# Robot_v2.net
KiCad netlist of a schematic drawn in EAGLE
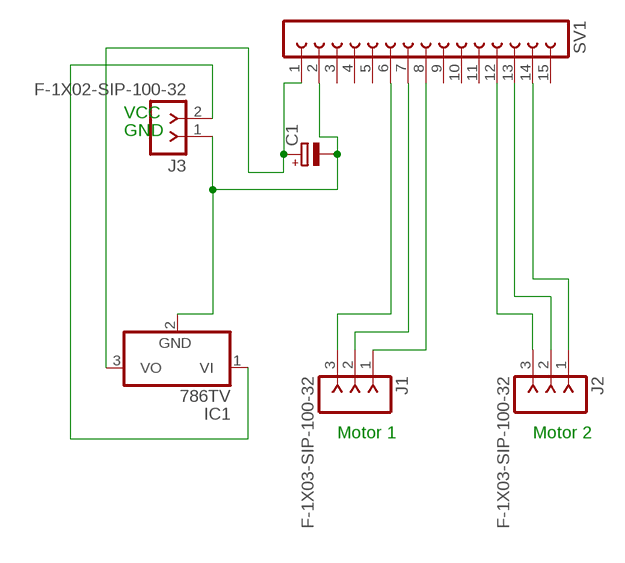
[diagram p0: schematic, sheet 1]

(export (version "E")
  (design (tool "Eeschema 10.0.6"))
  (components
    (comp (ref "C1")
      (value "CPOL-EUE1.8-4")
      (footprint "eagle-import:E1,8-4")
      (libsource (lib "eagle-import") (part "CPOL-EUE1.8-4"))
    )
    (comp (ref "IC1")
      (value "786TV")
      (footprint "eagle-import:TO220V")
      (libsource (lib "eagle-import") (part "78TV6"))
    )
    (comp (ref "J1")
      (value "F-1X03-SIP-100-32")
      (footprint "eagle-import:SIP-100-03-32")
      (libsource (lib "eagle-import") (part "F-1X03-SIP-100-32"))
    )
    (comp (ref "J2")
      (value "F-1X03-SIP-100-32")
      (footprint "eagle-import:SIP-100-03-32")
      (libsource (lib "eagle-import") (part "F-1X03-SIP-100-32"))
    )
    (comp (ref "J3")
      (value "F-1X02-SIP-100-32")
      (footprint "eagle-import:SIP-100-02-32")
      (libsource (lib "eagle-import") (part "F-1X02-SIP-100-32"))
    )
    (comp (ref "SV1")
      (value "FE15-1")
      (footprint "eagle-import:FE15")
      (libsource (lib "eagle-import") (part "FE15-1"))
    )
  )
  (nets
    (net (code "1") (name "Net-(IC1-GND)") (class "Default")
      (node (ref "C1") (pin "-") (pinfunction "-_-") (pintype "passive"))
      (node (ref "IC1") (pin "2") (pinfunction "GND_2") (pintype "passive"))
      (node (ref "J3") (pin "1") (pinfunction "1_1") (pintype "passive"))
      (node (ref "SV1") (pin "2") (pinfunction "2_2") (pintype "passive"))
    )
    (net (code "2") (name "Net-(IC1-VI)") (class "Default")
      (node (ref "IC1") (pin "1") (pinfunction "VI_1") (pintype "input"))
      (node (ref "J3") (pin "2") (pinfunction "2_2") (pintype "passive"))
    )
    (net (code "3") (name "Net-(IC1-VO)") (class "Default")
      (node (ref "C1") (pin "+") (pinfunction "+_+") (pintype "passive"))
      (node (ref "IC1") (pin "3") (pinfunction "VO_3") (pintype "passive"))
      (node (ref "SV1") (pin "1") (pinfunction "1_1") (pintype "passive"))
    )
    (net (code "4") (name "Net-(J1-Pad1)") (class "Default")
      (node (ref "J1") (pin "1") (pinfunction "1_1") (pintype "passive"))
      (node (ref "SV1") (pin "8") (pinfunction "8_8") (pintype "passive"))
    )
    (net (code "5") (name "Net-(J1-Pad2)") (class "Default")
      (node (ref "J1") (pin "2") (pinfunction "2_2") (pintype "passive"))
      (node (ref "SV1") (pin "7") (pinfunction "7_7") (pintype "passive"))
    )
    (net (code "6") (name "Net-(J1-Pad3)") (class "Default")
      (node (ref "J1") (pin "3") (pinfunction "3_3") (pintype "passive"))
      (node (ref "SV1") (pin "6") (pinfunction "6_6") (pintype "passive"))
    )
    (net (code "7") (name "Net-(J2-Pad1)") (class "Default")
      (node (ref "J2") (pin "1") (pinfunction "1_1") (pintype "passive"))
      (node (ref "SV1") (pin "14") (pinfunction "14_14") (pintype "passive"))
    )
    (net (code "8") (name "Net-(J2-Pad2)") (class "Default")
      (node (ref "J2") (pin "2") (pinfunction "2_2") (pintype "passive"))
      (node (ref "SV1") (pin "13") (pinfunction "13_13") (pintype "passive"))
    )
    (net (code "9") (name "Net-(J2-Pad3)") (class "Default")
      (node (ref "J2") (pin "3") (pinfunction "3_3") (pintype "passive"))
      (node (ref "SV1") (pin "12") (pinfunction "12_12") (pintype "passive"))
    )
    (net (code "10") (name "unconnected-(SV1-Pad3)") (class "Default")
      (node (ref "SV1") (pin "3") (pinfunction "3_3") (pintype "passive"))
    )
    (net (code "11") (name "unconnected-(SV1-Pad4)") (class "Default")
      (node (ref "SV1") (pin "4") (pinfunction "4_4") (pintype "passive"))
    )
    (net (code "12") (name "unconnected-(SV1-Pad5)") (class "Default")
      (node (ref "SV1") (pin "5") (pinfunction "5_5") (pintype "passive"))
    )
    (net (code "13") (name "unconnected-(SV1-Pad9)") (class "Default")
      (node (ref "SV1") (pin "9") (pinfunction "9_9") (pintype "passive"))
    )
    (net (code "14") (name "unconnected-(SV1-Pad10)") (class "Default")
      (node (ref "SV1") (pin "10") (pinfunction "10_10") (pintype "passive"))
    )
    (net (code "15") (name "unconnected-(SV1-Pad11)") (class "Default")
      (node (ref "SV1") (pin "11") (pinfunction "11_11") (pintype "passive"))
    )
    (net (code "16") (name "unconnected-(SV1-Pad15)") (class "Default")
      (node (ref "SV1") (pin "15") (pinfunction "15_15") (pintype "passive"))
    )
  )
)
